# Beleuchtung.net
KiCad netlist of a schematic drawn in Altium Designer
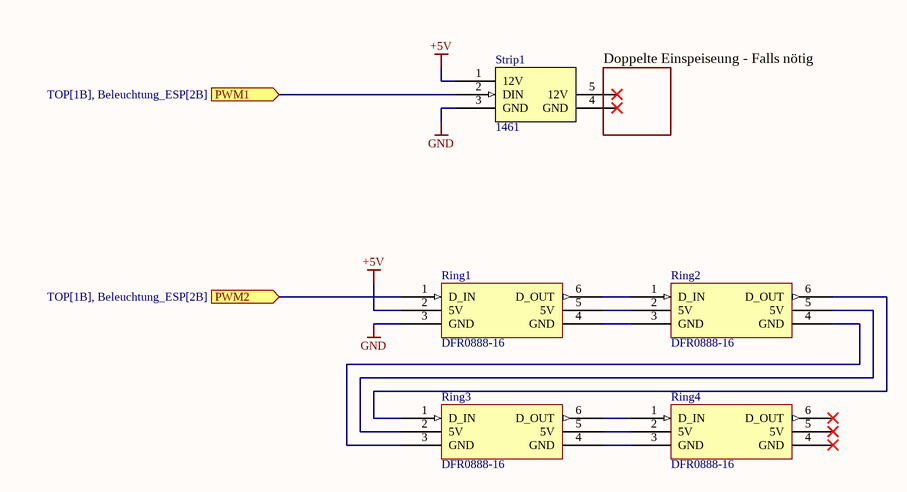
[diagram p0: Beleuchtung.SchDoc]

(export (version "E")
  (design (tool "Eeschema 10.0.6"))
  (components
    (comp (ref "Ring1")
      (value "DFR0888-16")
      (description "DFRobot, DFR0888-16.  \r\nWS2812-16 RGB LED RING LAMP")
      (libsource (lib "3D_Scanner") (part "RGB Ring"))
    )
    (comp (ref "Ring2")
      (value "DFR0888-16")
      (description "DFRobot, DFR0888-16.  \r\nWS2812-16 RGB LED RING LAMP")
      (libsource (lib "3D_Scanner") (part "RGB Ring"))
    )
    (comp (ref "Ring3")
      (value "DFR0888-16")
      (description "DFRobot, DFR0888-16.  \r\nWS2812-16 RGB LED RING LAMP")
      (libsource (lib "3D_Scanner") (part "RGB Ring"))
    )
    (comp (ref "Ring4")
      (value "DFR0888-16")
      (description "DFRobot, DFR0888-16.  \r\nWS2812-16 RGB LED RING LAMP")
      (libsource (lib "3D_Scanner") (part "RGB Ring"))
    )
    (comp (ref "Strip1")
      (value "1461")
      (description "ADDRESS LED STRIP SERIAL RGB 4M, Adafruit, 1461")
      (libsource (lib "3D_Scanner") (part "RGB Strip"))
    )
  )
  (nets
    (net (code "1") (name "+5V") (class "Default")
      (node (ref "Ring1") (pin "2") (pinfunction "5V_2") (pintype "power_in"))
      (node (ref "Strip1") (pin "1") (pinfunction "12V_1") (pintype "power_in"))
    )
    (net (code "2") (name "/PWM1") (class "Default")
      (node (ref "Strip1") (pin "2") (pinfunction "DIN_2") (pintype "input"))
    )
    (net (code "3") (name "/PWM2") (class "Default")
      (node (ref "Ring1") (pin "1") (pinfunction "D_IN_1") (pintype "input"))
    )
    (net (code "4") (name "GND") (class "Default")
      (node (ref "Ring1") (pin "3") (pinfunction "GND_3") (pintype "power_in"))
      (node (ref "Strip1") (pin "3") (pinfunction "GND_3") (pintype "power_in"))
    )
    (net (code "5") (name "Net-(Ring1-5V-Pad5)") (class "Default")
      (node (ref "Ring1") (pin "5") (pinfunction "5V_5") (pintype "power_in"))
      (node (ref "Ring2") (pin "2") (pinfunction "5V_2") (pintype "power_in"))
    )
    (net (code "6") (name "Net-(Ring1-D_OUT)") (class "Default")
      (node (ref "Ring1") (pin "6") (pinfunction "D_OUT_6") (pintype "output"))
      (node (ref "Ring2") (pin "1") (pinfunction "D_IN_1") (pintype "input"))
    )
    (net (code "7") (name "Net-(Ring1-GND-Pad4)") (class "Default")
      (node (ref "Ring1") (pin "4") (pinfunction "GND_4") (pintype "power_in"))
      (node (ref "Ring2") (pin "3") (pinfunction "GND_3") (pintype "power_in"))
    )
    (net (code "8") (name "Net-(Ring2-5V-Pad5)") (class "Default")
      (node (ref "Ring2") (pin "5") (pinfunction "5V_5") (pintype "power_in"))
      (node (ref "Ring3") (pin "2") (pinfunction "5V_2") (pintype "power_in"))
    )
    (net (code "9") (name "Net-(Ring2-D_OUT)") (class "Default")
      (node (ref "Ring2") (pin "6") (pinfunction "D_OUT_6") (pintype "output"))
      (node (ref "Ring3") (pin "1") (pinfunction "D_IN_1") (pintype "input"))
    )
    (net (code "10") (name "Net-(Ring2-GND-Pad4)") (class "Default")
      (node (ref "Ring2") (pin "4") (pinfunction "GND_4") (pintype "power_in"))
      (node (ref "Ring3") (pin "3") (pinfunction "GND_3") (pintype "power_in"))
    )
    (net (code "11") (name "Net-(Ring3-5V-Pad5)") (class "Default")
      (node (ref "Ring3") (pin "5") (pinfunction "5V_5") (pintype "power_in"))
      (node (ref "Ring4") (pin "2") (pinfunction "5V_2") (pintype "power_in"))
    )
    (net (code "12") (name "Net-(Ring3-D_OUT)") (class "Default")
      (node (ref "Ring3") (pin "6") (pinfunction "D_OUT_6") (pintype "output"))
      (node (ref "Ring4") (pin "1") (pinfunction "D_IN_1") (pintype "input"))
    )
    (net (code "13") (name "Net-(Ring3-GND-Pad4)") (class "Default")
      (node (ref "Ring3") (pin "4") (pinfunction "GND_4") (pintype "power_in"))
      (node (ref "Ring4") (pin "3") (pinfunction "GND_3") (pintype "power_in"))
    )
    (net (code "14") (name "unconnected-(Ring4-5V-Pad5)") (class "Default")
      (node (ref "Ring4") (pin "5") (pinfunction "5V_5") (pintype "power_in+no_connect"))
    )
    (net (code "15") (name "unconnected-(Ring4-D_OUT-Pad6)") (class "Default")
      (node (ref "Ring4") (pin "6") (pinfunction "D_OUT_6") (pintype "output+no_connect"))
    )
    (net (code "16") (name "unconnected-(Ring4-GND-Pad4)") (class "Default")
      (node (ref "Ring4") (pin "4") (pinfunction "GND_4") (pintype "power_in+no_connect"))
    )
    (net (code "17") (name "unconnected-(Strip1-12V-Pad5)") (class "Default")
      (node (ref "Strip1") (pin "5") (pinfunction "12V_5") (pintype "power_in+no_connect"))
    )
    (net (code "18") (name "unconnected-(Strip1-GND-Pad4)") (class "Default")
      (node (ref "Strip1") (pin "4") (pinfunction "GND_4") (pintype "power_in+no_connect"))
    )
  )
)
